# tiny85Digispark0805.net
KiCad netlist of a schematic drawn in EAGLE
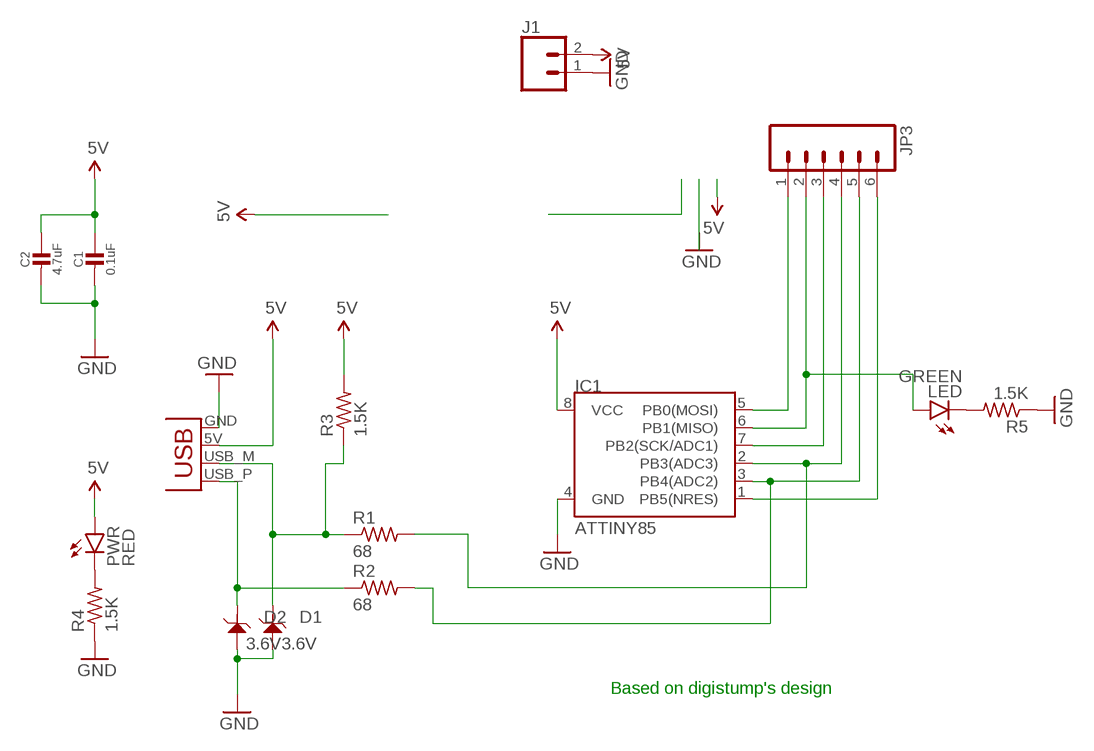
[diagram p0: schematic, sheet 1]

(export (version "E")
  (design (tool "Eeschema 10.0.6"))
  (components
    (comp (ref "C1")
      (value "0.1uF")
      (footprint "eagle-import:0805-NO")
      (libsource (lib "eagle-import") (part "CAP_CERAMIC0805-NOOUTLINE"))
    )
    (comp (ref "C2")
      (value "4.7uF")
      (footprint "eagle-import:0805-NO")
      (libsource (lib "eagle-import") (part "CAP_CERAMIC0805-NOOUTLINE"))
    )
    (comp (ref "D1")
      (value "3.6V")
      (footprint "eagle-import:SOD-123")
      (fields (field (name "MPN") "CESD5V0D1"))
      (libsource (lib "eagle-import") (part "SMD-DIODE-ESD-6.2V-250MW(SOD-123)"))
    )
    (comp (ref "D2")
      (value "3.6V")
      (footprint "eagle-import:SOD-123")
      (fields (field (name "MPN") "CESD5V0D1"))
      (libsource (lib "eagle-import") (part "SMD-DIODE-ESD-6.2V-250MW(SOD-123)"))
    )
    (comp (ref "IC1")
      (value "ATTINY85")
      (footprint "eagle-import:SO08-EIAJ")
      (libsource (lib "eagle-import") (part "ATTINY45"))
    )
    (comp (ref "J1")
      (value "CONN_02")
      (footprint "eagle-import:1X02")
      (libsource (lib "eagle-import") (part "CONN_02"))
    )
    (comp (ref "JP3")
      (value "M06SIP")
      (footprint "eagle-import:1X06")
      (libsource (lib "eagle-import") (part "M06SIP"))
    )
    (comp (ref "LED")
      (value "GREEN")
      (footprint "eagle-import:CHIP-LED0805")
      (libsource (lib "eagle-import") (part "LEDCHIP-LED0805"))
    )
    (comp (ref "PWR")
      (value "RED")
      (footprint "eagle-import:CHIP-LED0805")
      (libsource (lib "eagle-import") (part "LEDCHIP-LED0805"))
    )
    (comp (ref "R1")
      (value "68")
      (footprint "eagle-import:M0805")
      (libsource (lib "eagle-import") (part "R-US_M0805"))
    )
    (comp (ref "R2")
      (value "68")
      (footprint "eagle-import:M0805")
      (libsource (lib "eagle-import") (part "R-US_M0805"))
    )
    (comp (ref "R3")
      (value "1.5K")
      (footprint "eagle-import:M0805")
      (libsource (lib "eagle-import") (part "R-US_M0805"))
    )
    (comp (ref "R4")
      (value "1.5K")
      (footprint "eagle-import:M0805")
      (libsource (lib "eagle-import") (part "R-US_M0805"))
    )
    (comp (ref "R5")
      (value "1.5K")
      (footprint "eagle-import:M0805")
      (libsource (lib "eagle-import") (part "R-US_M0805"))
    )
    (comp (ref "X1")
      (value "USBPCB")
      (footprint "eagle-import:USB-A-PCB")
      (libsource (lib "eagle-import") (part "USBPCB"))
    )
  )
  (nets
    (net (code "1") (name "5V") (class "Default")
      (node (ref "C1") (pin "1") (pinfunction "1_1") (pintype "passive"))
      (node (ref "C2") (pin "1") (pinfunction "1_1") (pintype "passive"))
      (node (ref "IC1") (pin "8") (pinfunction "VCC_8") (pintype "bidirectional"))
      (node (ref "J1") (pin "2") (pinfunction "2_2") (pintype "passive"))
      (node (ref "PWR") (pin "A") (pinfunction "A_A") (pintype "passive"))
      (node (ref "R3") (pin "2") (pinfunction "2_2") (pintype "passive"))
      (node (ref "X1") (pin "5V") (pinfunction "VBUS_5V") (pintype "bidirectional"))
    )
    (net (code "2") (name "GND") (class "Default")
      (node (ref "C1") (pin "2") (pinfunction "2_2") (pintype "passive"))
      (node (ref "C2") (pin "2") (pinfunction "2_2") (pintype "passive"))
      (node (ref "D1") (pin "+") (pinfunction "1_+") (pintype "bidirectional"))
      (node (ref "D2") (pin "+") (pinfunction "1_+") (pintype "bidirectional"))
      (node (ref "IC1") (pin "4") (pinfunction "GND_4") (pintype "bidirectional"))
      (node (ref "J1") (pin "1") (pinfunction "1_1") (pintype "passive"))
      (node (ref "R4") (pin "1") (pinfunction "1_1") (pintype "passive"))
      (node (ref "R5") (pin "1") (pinfunction "1_1") (pintype "passive"))
      (node (ref "X1") (pin "GND") (pinfunction "GND_GND") (pintype "bidirectional"))
    )
    (net (code "3") (name "Net-(D1-2)") (class "Default")
      (node (ref "D1") (pin "-") (pinfunction "2_-") (pintype "bidirectional"))
      (node (ref "R1") (pin "1") (pinfunction "1_1") (pintype "passive"))
      (node (ref "R3") (pin "1") (pinfunction "1_1") (pintype "passive"))
      (node (ref "X1") (pin "USB_M") (pinfunction "D-_USB_M") (pintype "bidirectional"))
    )
    (net (code "4") (name "Net-(D2-2)") (class "Default")
      (node (ref "D2") (pin "-") (pinfunction "2_-") (pintype "bidirectional"))
      (node (ref "R2") (pin "1") (pinfunction "1_1") (pintype "passive"))
      (node (ref "X1") (pin "USB_P") (pinfunction "D+_USB_P") (pintype "bidirectional"))
    )
    (net (code "5") (name "Net-(IC1-PB0(MOSI))") (class "Default")
      (node (ref "IC1") (pin "5") (pinfunction "PB0(MOSI)_5") (pintype "bidirectional"))
      (node (ref "JP3") (pin "1") (pinfunction "1_1") (pintype "passive"))
    )
    (net (code "6") (name "Net-(IC1-PB1(MISO))") (class "Default")
      (node (ref "IC1") (pin "6") (pinfunction "PB1(MISO)_6") (pintype "bidirectional"))
      (node (ref "JP3") (pin "2") (pinfunction "2_2") (pintype "passive"))
      (node (ref "LED") (pin "A") (pinfunction "A_A") (pintype "passive"))
    )
    (net (code "7") (name "Net-(IC1-PB2(SCK{slash}ADC1))") (class "Default")
      (node (ref "IC1") (pin "7") (pinfunction "PB2(SCK/ADC1)_7") (pintype "bidirectional"))
      (node (ref "JP3") (pin "3") (pinfunction "3_3") (pintype "passive"))
    )
    (net (code "8") (name "Net-(IC1-PB3(ADC3))") (class "Default")
      (node (ref "IC1") (pin "2") (pinfunction "PB3(ADC3)_2") (pintype "bidirectional"))
      (node (ref "JP3") (pin "4") (pinfunction "4_4") (pintype "passive"))
      (node (ref "R1") (pin "2") (pinfunction "2_2") (pintype "passive"))
    )
    (net (code "9") (name "Net-(IC1-PB4(ADC2))") (class "Default")
      (node (ref "IC1") (pin "3") (pinfunction "PB4(ADC2)_3") (pintype "bidirectional"))
      (node (ref "JP3") (pin "5") (pinfunction "5_5") (pintype "passive"))
      (node (ref "R2") (pin "2") (pinfunction "2_2") (pintype "passive"))
    )
    (net (code "10") (name "Net-(IC1-PB5(NRES))") (class "Default")
      (node (ref "IC1") (pin "1") (pinfunction "PB5(NRES)_1") (pintype "bidirectional"))
      (node (ref "JP3") (pin "6") (pinfunction "6_6") (pintype "passive"))
    )
    (net (code "11") (name "Net-(LED-PadC)") (class "Default")
      (node (ref "LED") (pin "C") (pinfunction "C_C") (pintype "passive"))
      (node (ref "R5") (pin "2") (pinfunction "2_2") (pintype "passive"))
    )
    (net (code "12") (name "Net-(PWR-PadC)") (class "Default")
      (node (ref "PWR") (pin "C") (pinfunction "C_C") (pintype "passive"))
      (node (ref "R4") (pin "2") (pinfunction "2_2") (pintype "passive"))
    )
  )
)
